# MPPT_Measurements.net
KiCad netlist of a schematic drawn in Altium Designer
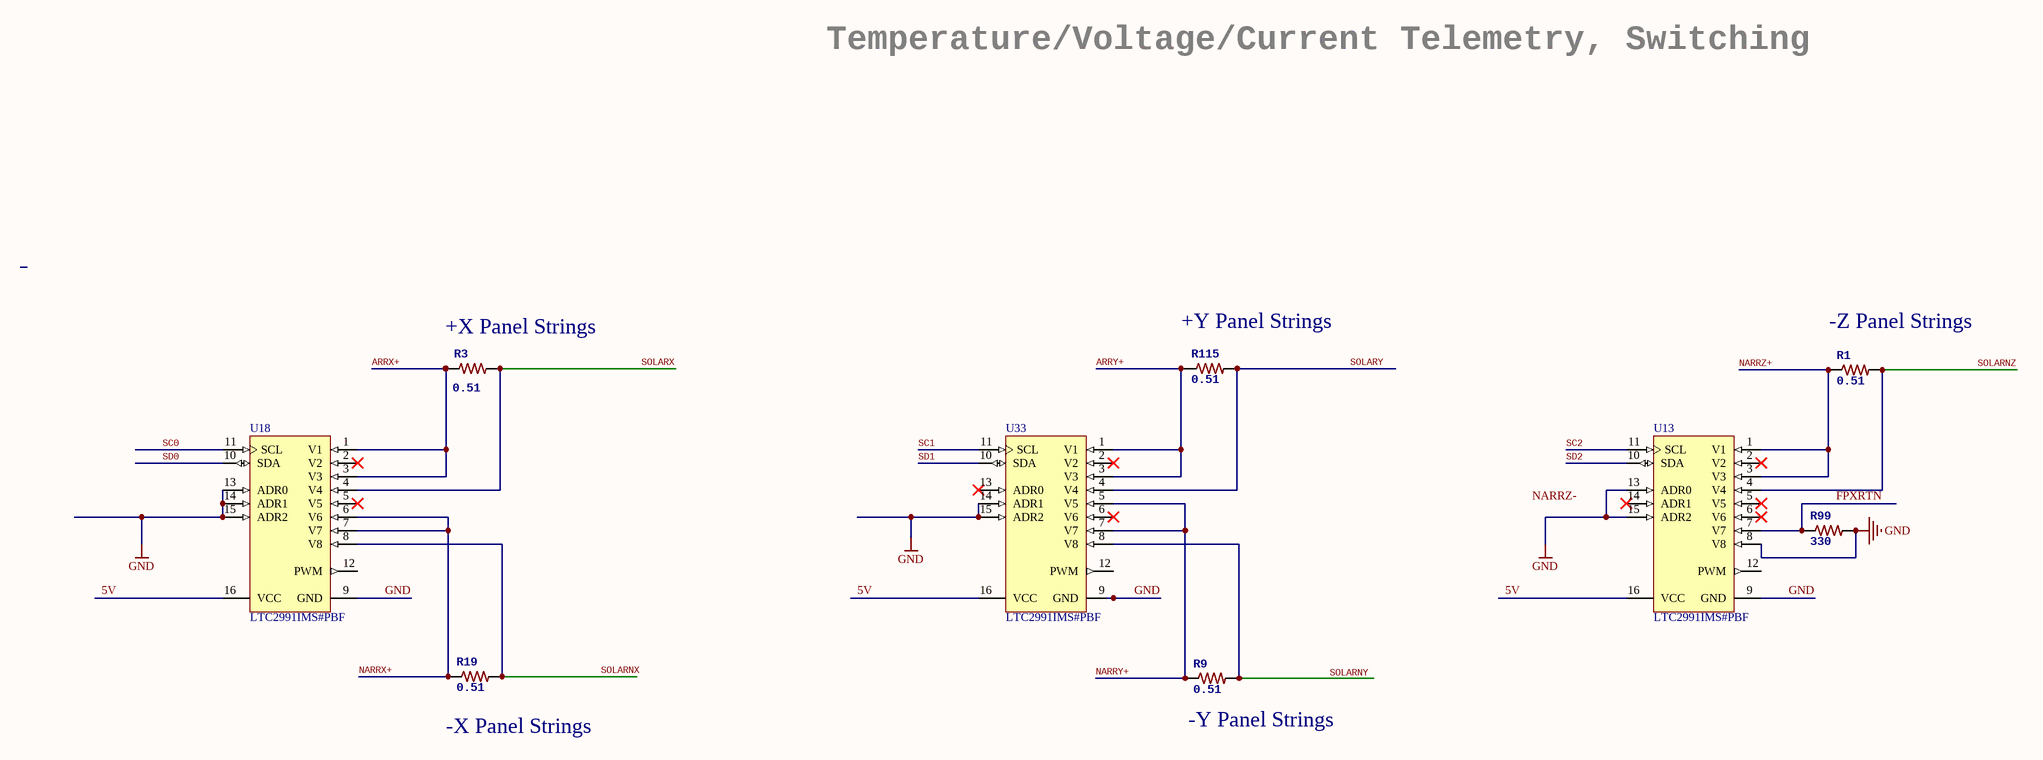
[diagram p0: MPPT_Measurements.SchDoc]

(export (version "E")
  (design (tool "Eeschema 10.0.6"))
  (components
    (comp (ref "R1")
      (value "0.51")
      (footprint "RESC1220X06N")
      (description "<b>Resistor</b>\nBasic schematic elements and footprints for 0603, 1206, and PTH resistors.")
      (libsource (lib "yusend_power") (part "RESISTOR"))
    )
    (comp (ref "R3")
      (value "0.51")
      (footprint "RESC1220X06N")
      (description "<b>Resistor</b>\nBasic schematic elements and footprints for 0603, 1206, and PTH resistors.")
      (libsource (lib "yusend_power") (part "RESISTOR"))
    )
    (comp (ref "R9")
      (value "0.51")
      (footprint "RESC1220X06N")
      (description "<b>Resistor</b>\nBasic schematic elements and footprints for 0603, 1206, and PTH resistors.")
      (libsource (lib "yusend_power") (part "RESISTOR"))
    )
    (comp (ref "R19")
      (value "0.51")
      (footprint "RESC1220X06N")
      (description "<b>Resistor</b>\nBasic schematic elements and footprints for 0603, 1206, and PTH resistors.")
      (libsource (lib "yusend_power") (part "RESISTOR"))
    )
    (comp (ref "R99")
      (value "330")
      (footprint "0603-RES")
      (fields
        (field (name "MANUFACTURER") "TE Connectivity")
        (field (name "MANUFACTURER PART NUMBER") "1625856-2")
        (field (name "TOLERANCE") "±10%")
      )
      (libsource (lib "yusend_power") (part "RESISTOR0805-RES_333"))
    )
    (comp (ref "R115")
      (value "0.51")
      (footprint "RESC1220X06N")
      (description "<b>Resistor</b>\nBasic schematic elements and footprints for 0603, 1206, and PTH resistors.")
      (libsource (lib "yusend_power") (part "RESISTOR"))
    )
    (comp (ref "U13")
      (value "LTC2991IMS#PBF")
      (footprint "LT-MS-16_N")
      (description "Octal I2C Voltage, Current, and Temperature Monitor, 16-pin SOP (MS-16), -40 to 85 degC, Pb-Free")
      (fields (field (name "MANUFACTURER") "Linear Technology"))
      (libsource (lib "Altium Content Vault") (part "LT-LTC2991-MS-16"))
    )
    (comp (ref "U18")
      (value "LTC2991IMS#PBF")
      (footprint "LT-MS-16_N")
      (description "Octal I2C Voltage, Current, and Temperature Monitor, 16-pin SOP (MS-16), -40 to 85 degC, Pb-Free")
      (fields (field (name "MANUFACTURER") "Linear Technology"))
      (libsource (lib "Altium Content Vault") (part "LT-LTC2991-MS-16"))
    )
    (comp (ref "U33")
      (value "LTC2991IMS#PBF")
      (footprint "LT-MS-16_N")
      (description "Octal I2C Voltage, Current, and Temperature Monitor, 16-pin SOP (MS-16), -40 to 85 degC, Pb-Free")
      (fields (field (name "MANUFACTURER") "Linear Technology"))
      (libsource (lib "Altium Content Vault") (part "LT-LTC2991-MS-16"))
    )
  )
  (nets
    (net (code "1") (name "/5V") (class "Default")
      (node (ref "U13") (pin "16") (pinfunction "VCC_16") (pintype "power_in"))
      (node (ref "U18") (pin "16") (pinfunction "VCC_16") (pintype "power_in"))
      (node (ref "U33") (pin "16") (pinfunction "VCC_16") (pintype "power_in"))
    )
    (net (code "2") (name "/ARRX+") (class "Default")
      (node (ref "R3") (pin "1") (pinfunction "1_1") (pintype "passive"))
      (node (ref "U18") (pin "1") (pinfunction "V1_1") (pintype "input"))
      (node (ref "U18") (pin "3") (pinfunction "V3_3") (pintype "input"))
    )
    (net (code "3") (name "/ARRY+") (class "Default")
      (node (ref "R115") (pin "1") (pinfunction "1_1") (pintype "passive"))
      (node (ref "U33") (pin "1") (pinfunction "V1_1") (pintype "input"))
      (node (ref "U33") (pin "3") (pinfunction "V3_3") (pintype "input"))
    )
    (net (code "4") (name "/FPXRTN") (class "Default")
      (node (ref "R99") (pin "1") (pinfunction "1_1") (pintype "passive"))
      (node (ref "U13") (pin "7") (pinfunction "V7_7") (pintype "input"))
    )
    (net (code "5") (name "/NARRX+") (class "Default")
      (node (ref "R19") (pin "1") (pinfunction "1_1") (pintype "passive"))
      (node (ref "U18") (pin "6") (pinfunction "V6_6") (pintype "input"))
      (node (ref "U18") (pin "7") (pinfunction "V7_7") (pintype "input"))
    )
    (net (code "6") (name "/NARRY+") (class "Default")
      (node (ref "R9") (pin "1") (pinfunction "1_1") (pintype "passive"))
      (node (ref "U33") (pin "5") (pinfunction "V5_5") (pintype "input"))
      (node (ref "U33") (pin "7") (pinfunction "V7_7") (pintype "input"))
    )
    (net (code "7") (name "/NARRZ+") (class "Default")
      (node (ref "R1") (pin "1") (pinfunction "1_1") (pintype "passive"))
      (node (ref "U13") (pin "1") (pinfunction "V1_1") (pintype "input"))
      (node (ref "U13") (pin "3") (pinfunction "V3_3") (pintype "input"))
    )
    (net (code "9") (name "/SC0") (class "Default")
      (node (ref "U18") (pin "11") (pinfunction "SCL_11") (pintype "input"))
    )
    (net (code "10") (name "/SC1") (class "Default")
      (node (ref "U33") (pin "11") (pinfunction "SCL_11") (pintype "input"))
    )
    (net (code "11") (name "/SC2") (class "Default")
      (node (ref "U13") (pin "11") (pinfunction "SCL_11") (pintype "input"))
    )
    (net (code "12") (name "/SD0") (class "Default")
      (node (ref "U18") (pin "10") (pinfunction "SDA_10") (pintype "bidirectional"))
    )
    (net (code "13") (name "/SD1") (class "Default")
      (node (ref "U33") (pin "10") (pinfunction "SDA_10") (pintype "bidirectional"))
    )
    (net (code "14") (name "/SD2") (class "Default")
      (node (ref "U13") (pin "10") (pinfunction "SDA_10") (pintype "bidirectional"))
    )
    (net (code "15") (name "/SOLARNX") (class "Default")
      (node (ref "R19") (pin "2") (pinfunction "2_2") (pintype "passive"))
      (node (ref "U18") (pin "8") (pinfunction "V8_8") (pintype "input"))
    )
    (net (code "17") (name "/SOLARNZ") (class "Default")
      (node (ref "R1") (pin "2") (pinfunction "2_2") (pintype "passive"))
      (node (ref "U13") (pin "4") (pinfunction "V4_4") (pintype "input"))
    )
    (net (code "18") (name "/SOLARX") (class "Default")
      (node (ref "R3") (pin "2") (pinfunction "2_2") (pintype "passive"))
      (node (ref "U18") (pin "4") (pinfunction "V4_4") (pintype "input"))
    )
    (net (code "19") (name "/SOLARY") (class "Default")
      (node (ref "R115") (pin "2") (pinfunction "2_2") (pintype "passive"))
      (node (ref "U33") (pin "4") (pinfunction "V4_4") (pintype "input"))
    )
    (net (code "20") (name "GND") (class "Default")
      (node (ref "R99") (pin "2") (pinfunction "2_2") (pintype "passive"))
      (node (ref "U13") (pin "13") (pinfunction "ADR0_13") (pintype "input"))
      (node (ref "U13") (pin "15") (pinfunction "ADR2_15") (pintype "input"))
      (node (ref "U13") (pin "8") (pinfunction "V8_8") (pintype "input"))
      (node (ref "U13") (pin "9") (pinfunction "GND_9") (pintype "power_in"))
      (node (ref "U18") (pin "13") (pinfunction "ADR0_13") (pintype "input"))
      (node (ref "U18") (pin "14") (pinfunction "ADR1_14") (pintype "input"))
      (node (ref "U18") (pin "15") (pinfunction "ADR2_15") (pintype "input"))
      (node (ref "U18") (pin "9") (pinfunction "GND_9") (pintype "power_in"))
      (node (ref "U33") (pin "14") (pinfunction "ADR1_14") (pintype "input"))
      (node (ref "U33") (pin "15") (pinfunction "ADR2_15") (pintype "input"))
      (node (ref "U33") (pin "9") (pinfunction "GND_9") (pintype "power_in"))
    )
    (net (code "21") (name "Net-(U33-V8)") (class "Default")
      (node (ref "R9") (pin "2") (pinfunction "2_2") (pintype "passive"))
      (node (ref "U33") (pin "8") (pinfunction "V8_8") (pintype "input"))
    )
    (net (code "22") (name "unconnected-(U13-ADR1-Pad14)") (class "Default")
      (node (ref "U13") (pin "14") (pinfunction "ADR1_14") (pintype "input+no_connect"))
    )
    (net (code "23") (name "unconnected-(U13-PWM-Pad12)") (class "Default")
      (node (ref "U13") (pin "12") (pinfunction "PWM_12") (pintype "output"))
    )
    (net (code "24") (name "unconnected-(U13-V2-Pad2)") (class "Default")
      (node (ref "U13") (pin "2") (pinfunction "V2_2") (pintype "input+no_connect"))
    )
    (net (code "25") (name "unconnected-(U13-V5-Pad5)") (class "Default")
      (node (ref "U13") (pin "5") (pinfunction "V5_5") (pintype "input+no_connect"))
    )
    (net (code "26") (name "unconnected-(U13-V6-Pad6)") (class "Default")
      (node (ref "U13") (pin "6") (pinfunction "V6_6") (pintype "input+no_connect"))
    )
    (net (code "27") (name "unconnected-(U18-PWM-Pad12)") (class "Default")
      (node (ref "U18") (pin "12") (pinfunction "PWM_12") (pintype "output"))
    )
    (net (code "28") (name "unconnected-(U18-V2-Pad2)") (class "Default")
      (node (ref "U18") (pin "2") (pinfunction "V2_2") (pintype "input+no_connect"))
    )
    (net (code "29") (name "unconnected-(U18-V5-Pad5)") (class "Default")
      (node (ref "U18") (pin "5") (pinfunction "V5_5") (pintype "input+no_connect"))
    )
    (net (code "30") (name "unconnected-(U33-ADR0-Pad13)") (class "Default")
      (node (ref "U33") (pin "13") (pinfunction "ADR0_13") (pintype "input+no_connect"))
    )
    (net (code "31") (name "unconnected-(U33-PWM-Pad12)") (class "Default")
      (node (ref "U33") (pin "12") (pinfunction "PWM_12") (pintype "output"))
    )
    (net (code "32") (name "unconnected-(U33-V2-Pad2)") (class "Default")
      (node (ref "U33") (pin "2") (pinfunction "V2_2") (pintype "input+no_connect"))
    )
    (net (code "33") (name "unconnected-(U33-V6-Pad6)") (class "Default")
      (node (ref "U33") (pin "6") (pinfunction "V6_6") (pintype "input+no_connect"))
    )
  )
)
